# Mixer_to_LP-HP_Filter.net
KiCad netlist of a schematic drawn in Altium Designer
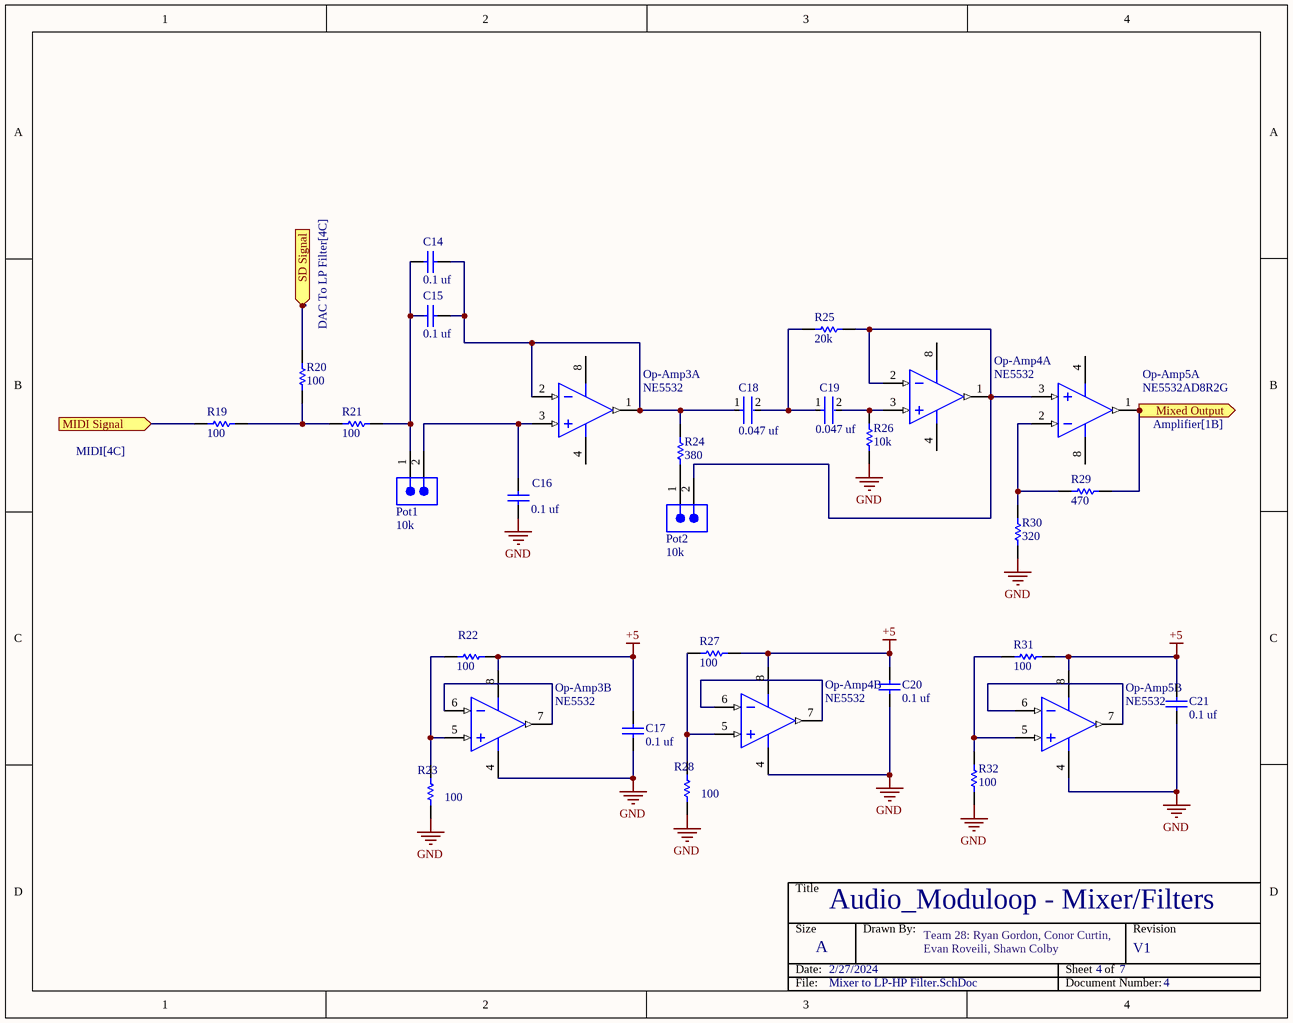
[diagram p0: Mixer to LP-HP Filter.SchDoc]

(export (version "E")
  (design (tool "Eeschema 10.0.6"))
  (components
    (comp (ref "C14")
      (value "0.1 uf")
      (footprint "AVX-SA115C104KAR")
      (fields (field (name "TOLERANCE") "±10%") (field (name "MANUFACTURER") "AVX"))
      (libsource (lib "Altium Content Vault") (part "CAP-NP-2"))
    )
    (comp (ref "C15")
      (value "0.1 uf")
      (footprint "AVX-SA115C104KAR")
      (fields (field (name "TOLERANCE") "±10%") (field (name "MANUFACTURER") "AVX"))
      (libsource (lib "Altium Content Vault") (part "CAP-NP-2"))
    )
    (comp (ref "C16")
      (value "0.1 uf")
      (footprint "AVX-SA115C104KAR")
      (fields (field (name "TOLERANCE") "±10%") (field (name "MANUFACTURER") "AVX"))
      (libsource (lib "Altium Content Vault") (part "CAP-NP-2"))
    )
    (comp (ref "C17")
      (value "0.1 uf")
      (footprint "AVX-SA115C104KAR")
      (fields (field (name "TOLERANCE") "±10%") (field (name "MANUFACTURER") "AVX"))
      (libsource (lib "Altium Content Vault") (part "CAP-NP-2"))
    )
    (comp (ref "C18")
      (value "0.047 uf")
      (footprint "FP-RCE1K1-2_5-MFG")
      (description "Cap Ceramic Monolithic 47nF 100V 10% Thru-Hole Bulk")
      (fields (field (name "TOLERANCE") "10%"))
      (libsource (lib "Altium Content Vault") (part "02cd4be3c70576c341d710602a673aa"))
    )
    (comp (ref "C19")
      (value "0.047 uf")
      (footprint "FP-RCE1K1-2_5-MFG")
      (description "Cap Ceramic Monolithic 47nF 100V 10% Thru-Hole Bulk")
      (fields (field (name "TOLERANCE") "10%"))
      (libsource (lib "Altium Content Vault") (part "02cd4be3c70576c341d710602a673aa"))
    )
    (comp (ref "C20")
      (value "0.1 uf")
      (footprint "AVX-SA115C104KAR")
      (fields (field (name "TOLERANCE") "±10%") (field (name "MANUFACTURER") "AVX"))
      (libsource (lib "Altium Content Vault") (part "CAP-NP-2"))
    )
    (comp (ref "C21")
      (value "0.1 uf")
      (footprint "AVX-SA115C104KAR")
      (fields (field (name "TOLERANCE") "±10%") (field (name "MANUFACTURER") "AVX"))
      (libsource (lib "Altium Content Vault") (part "CAP-NP-2"))
    )
    (comp (ref "Op-Amp3")
      (value "NE5532")
      (footprint "ONSC-SOIC-8-751-07_V")
      (fields (field (name "MANUFACTURER") "On Semiconductor") (field (name "PARTNUMBER") "NE5532AD8R2G"))
      (libsource (lib "Altium Content Vault") (part "ONSC-NE5532-SOIC-8-751-07"))
    )
    (comp (ref "Op-Amp4")
      (value "NE5532")
      (footprint "ONSC-SOIC-8-751-07_V")
      (fields (field (name "MANUFACTURER") "On Semiconductor") (field (name "PARTNUMBER") "NE5532AD8R2G"))
      (libsource (lib "Altium Content Vault") (part "ONSC-NE5532-SOIC-8-751-07"))
    )
    (comp (ref "Op-Amp5")
      (value "NE5532AD8R2G")
      (footprint "ONSC-SOIC-8-751-07_V")
      (fields (field (name "MANUFACTURER") "On Semiconductor") (field (name "PARTNUMBER") "NE5532AD8R2G"))
      (libsource (lib "Altium Content Vault") (part "ONSC-NE5532-SOIC-8-751-07"))
    )
    (comp (ref "Pot1")
      (value "10k")
      (footprint "61300211121")
      (libsource (lib "Altium Content Vault") (part "Header_Male_1R_02P"))
    )
    (comp (ref "Pot2")
      (value "10k")
      (footprint "61300211121")
      (libsource (lib "Altium Content Vault") (part "Header_Male_1R_02P"))
    )
    (comp (ref "R19")
      (value "100")
      (footprint "RESC2013X60X40ML20T25")
      (fields (field (name "MANUFACTURER") "Panasonic") (field (name "PART NUMBER") "ERA6AEB101V"))
      (libsource (lib "Altium Content Vault") (part "RES"))
    )
    (comp (ref "R20")
      (value "100")
      (footprint "RESC2013X60X40ML20T25")
      (fields (field (name "MANUFACTURER") "Panasonic") (field (name "PART NUMBER") "ERA6AEB101V"))
      (libsource (lib "Altium Content Vault") (part "RES"))
    )
    (comp (ref "R21")
      (value "100")
      (footprint "RESC2013X60X40ML20T25")
      (fields (field (name "MANUFACTURER") "Panasonic") (field (name "PART NUMBER") "ERA6AEB101V"))
      (libsource (lib "Altium Content Vault") (part "RES"))
    )
    (comp (ref "R22")
      (value "100")
      (footprint "RESC2013X60X40ML20T25")
      (fields (field (name "MANUFACTURER") "Panasonic") (field (name "PART NUMBER") "ERA6AEB101V"))
      (libsource (lib "Altium Content Vault") (part "RES"))
    )
    (comp (ref "R23")
      (value "100")
      (footprint "RESC2013X60X40ML20T25")
      (fields (field (name "MANUFACTURER") "Panasonic") (field (name "PART NUMBER") "ERA6AEB101V"))
      (libsource (lib "Altium Content Vault") (part "RES"))
    )
    (comp (ref "R24")
      (value "380")
      (footprint "RESC2013X60X40LL20T25")
      (fields (field (name "MANUFACTURER") "Panasonic") (field (name "PART NUMBER") "ERA6AEB331V"))
      (libsource (lib "Altium Content Vault") (part "RES"))
    )
    (comp (ref "R25")
      (value "20k")
      (footprint "RESC2013X60X35NL10T20")
      (description "Chip Resistor, 10 KOhm, +/- 1%, 0.125 W, -55 to 155 degC, 0805 (2012 Metric), RoHS, Tape and Reel")
      (fields (field (name "MANUFACTURER") "Yageo"))
      (libsource (lib "Altium Content Vault") (part "RES-2"))
    )
    (comp (ref "R26")
      (value "10k")
      (footprint "RESC2013X60X35NL10T20")
      (description "Chip Resistor, 10 KOhm, +/- 1%, 0.125 W, -55 to 155 degC, 0805 (2012 Metric), RoHS, Tape and Reel")
      (fields (field (name "MANUFACTURER") "Yageo"))
      (libsource (lib "Altium Content Vault") (part "RES-2"))
    )
    (comp (ref "R27")
      (value "100")
      (footprint "RESC2013X60X40ML20T25")
      (fields (field (name "MANUFACTURER") "Panasonic") (field (name "PART NUMBER") "ERA6AEB101V"))
      (libsource (lib "Altium Content Vault") (part "RES"))
    )
    (comp (ref "R28")
      (value "100")
      (footprint "RESC2013X60X40ML20T25")
      (fields (field (name "MANUFACTURER") "Panasonic") (field (name "PART NUMBER") "ERA6AEB101V"))
      (libsource (lib "Altium Content Vault") (part "RES"))
    )
    (comp (ref "R29")
      (value "470")
      (footprint "RESC2013X60X40NL20T25")
      (fields (field (name "PART NUMBER") "ERA6AEB471V") (field (name "MANUFACTURER") "Panasonic"))
      (libsource (lib "Altium Content Vault") (part "RES"))
    )
    (comp (ref "R30")
      (value "320")
      (footprint "RESC2013X60X40LL20T25")
      (fields (field (name "MANUFACTURER") "Panasonic") (field (name "PART NUMBER") "ERA6AEB331V"))
      (libsource (lib "Altium Content Vault") (part "RES"))
    )
    (comp (ref "R31")
      (value "100")
      (footprint "RESC2013X60X40ML20T25")
      (fields (field (name "MANUFACTURER") "Panasonic") (field (name "PART NUMBER") "ERA6AEB101V"))
      (libsource (lib "Altium Content Vault") (part "RES"))
    )
    (comp (ref "R32")
      (value "100")
      (footprint "RESC2013X60X40ML20T25")
      (fields (field (name "MANUFACTURER") "Panasonic") (field (name "PART NUMBER") "ERA6AEB101V"))
      (libsource (lib "Altium Content Vault") (part "RES"))
    )
  )
  (nets
    (net (code "1") (name "+5") (class "Default")
      (node (ref "C17") (pin "2") (pinfunction "2_2") (pintype "passive"))
      (node (ref "C20") (pin "2") (pinfunction "2_2") (pintype "passive"))
      (node (ref "C21") (pin "2") (pinfunction "2_2") (pintype "passive"))
      (node (ref "Op-Amp3") (pin "8") (pinfunction "V+_8") (pintype "power_in"))
      (node (ref "Op-Amp4") (pin "8") (pinfunction "V+_8") (pintype "power_in"))
      (node (ref "Op-Amp5") (pin "8") (pinfunction "V+_8") (pintype "power_in"))
      (node (ref "R22") (pin "1") (pinfunction "1_1") (pintype "passive"))
      (node (ref "R27") (pin "1") (pinfunction "1_1") (pintype "passive"))
      (node (ref "R31") (pin "1") (pinfunction "1_1") (pintype "passive"))
    )
    (net (code "2") (name "/MIDI Signal") (class "Default")
      (node (ref "R19") (pin "1") (pinfunction "1_1") (pintype "passive"))
    )
    (net (code "3") (name "/Mixed Output") (class "Default")
      (node (ref "Op-Amp5") (pin "1") (pinfunction "OUTA_1") (pintype "output"))
      (node (ref "R29") (pin "2") (pinfunction "2_2") (pintype "passive"))
    )
    (net (code "4") (name "/SD Signal") (class "Default")
      (node (ref "R20") (pin "1") (pinfunction "1_1") (pintype "passive"))
    )
    (net (code "5") (name "GND") (class "Default")
      (node (ref "C16") (pin "1") (pinfunction "1_1") (pintype "passive"))
      (node (ref "C17") (pin "1") (pinfunction "1_1") (pintype "passive"))
      (node (ref "C20") (pin "1") (pinfunction "1_1") (pintype "passive"))
      (node (ref "C21") (pin "1") (pinfunction "1_1") (pintype "passive"))
      (node (ref "Op-Amp3") (pin "4") (pinfunction "V-_4") (pintype "power_in"))
      (node (ref "Op-Amp4") (pin "4") (pinfunction "V-_4") (pintype "power_in"))
      (node (ref "Op-Amp5") (pin "4") (pinfunction "V-_4") (pintype "power_in"))
      (node (ref "R23") (pin "1") (pinfunction "1_1") (pintype "passive"))
      (node (ref "R26") (pin "2") (pinfunction "2_2") (pintype "passive"))
      (node (ref "R28") (pin "1") (pinfunction "1_1") (pintype "passive"))
      (node (ref "R30") (pin "2") (pinfunction "2_2") (pintype "passive"))
      (node (ref "R32") (pin "2") (pinfunction "2_2") (pintype "passive"))
    )
    (net (code "6") (name "Net-(C14-Pad1)") (class "Default")
      (node (ref "C14") (pin "1") (pinfunction "1_1") (pintype "passive"))
      (node (ref "C15") (pin "1") (pinfunction "1_1") (pintype "passive"))
      (node (ref "Pot1") (pin "1") (pinfunction "1_1") (pintype "passive"))
      (node (ref "R21") (pin "1") (pinfunction "1_1") (pintype "passive"))
    )
    (net (code "7") (name "Net-(C18-Pad2)") (class "Default")
      (node (ref "C18") (pin "2") (pinfunction "2_2") (pintype "passive"))
      (node (ref "C19") (pin "1") (pinfunction "1_1") (pintype "passive"))
      (node (ref "R25") (pin "1") (pinfunction "1_1") (pintype "passive"))
    )
    (net (code "8") (name "Net-(Op-Amp3A-INA+)") (class "Default")
      (node (ref "C16") (pin "2") (pinfunction "2_2") (pintype "passive"))
      (node (ref "Op-Amp3") (pin "3") (pinfunction "INA+_3") (pintype "input"))
      (node (ref "Pot1") (pin "2") (pinfunction "2_2") (pintype "passive"))
    )
    (net (code "9") (name "Net-(Op-Amp3A-INA-)") (class "Default")
      (node (ref "C14") (pin "2") (pinfunction "2_2") (pintype "passive"))
      (node (ref "C15") (pin "2") (pinfunction "2_2") (pintype "passive"))
      (node (ref "C18") (pin "1") (pinfunction "1_1") (pintype "passive"))
      (node (ref "Op-Amp3") (pin "1") (pinfunction "OUTA_1") (pintype "output"))
      (node (ref "Op-Amp3") (pin "2") (pinfunction "INA-_2") (pintype "input"))
      (node (ref "R24") (pin "1") (pinfunction "1_1") (pintype "passive"))
    )
    (net (code "10") (name "Net-(Op-Amp3B-INB+)") (class "Default")
      (node (ref "Op-Amp3") (pin "5") (pinfunction "INB+_5") (pintype "input"))
      (node (ref "R22") (pin "2") (pinfunction "2_2") (pintype "passive"))
      (node (ref "R23") (pin "2") (pinfunction "2_2") (pintype "passive"))
    )
    (net (code "11") (name "Net-(Op-Amp3B-INB-)") (class "Default")
      (node (ref "Op-Amp3") (pin "6") (pinfunction "INB-_6") (pintype "input"))
      (node (ref "Op-Amp3") (pin "7") (pinfunction "OUTB_7") (pintype "output"))
    )
    (net (code "12") (name "Net-(Op-Amp4A-INA+)") (class "Default")
      (node (ref "C19") (pin "2") (pinfunction "2_2") (pintype "passive"))
      (node (ref "Op-Amp4") (pin "3") (pinfunction "INA+_3") (pintype "input"))
      (node (ref "R26") (pin "1") (pinfunction "1_1") (pintype "passive"))
    )
    (net (code "13") (name "Net-(Op-Amp4A-INA-)") (class "Default")
      (node (ref "Op-Amp4") (pin "1") (pinfunction "OUTA_1") (pintype "output"))
      (node (ref "Op-Amp4") (pin "2") (pinfunction "INA-_2") (pintype "input"))
      (node (ref "Op-Amp5") (pin "3") (pinfunction "INA+_3") (pintype "input"))
      (node (ref "Pot2") (pin "2") (pinfunction "2_2") (pintype "passive"))
      (node (ref "R25") (pin "2") (pinfunction "2_2") (pintype "passive"))
    )
    (net (code "14") (name "Net-(Op-Amp4B-INB+)") (class "Default")
      (node (ref "Op-Amp4") (pin "5") (pinfunction "INB+_5") (pintype "input"))
      (node (ref "R27") (pin "2") (pinfunction "2_2") (pintype "passive"))
      (node (ref "R28") (pin "2") (pinfunction "2_2") (pintype "passive"))
    )
    (net (code "15") (name "Net-(Op-Amp4B-INB-)") (class "Default")
      (node (ref "Op-Amp4") (pin "6") (pinfunction "INB-_6") (pintype "input"))
      (node (ref "Op-Amp4") (pin "7") (pinfunction "OUTB_7") (pintype "output"))
    )
    (net (code "16") (name "Net-(Op-Amp5A-INA-)") (class "Default")
      (node (ref "Op-Amp5") (pin "2") (pinfunction "INA-_2") (pintype "input"))
      (node (ref "R29") (pin "1") (pinfunction "1_1") (pintype "passive"))
      (node (ref "R30") (pin "1") (pinfunction "1_1") (pintype "passive"))
    )
    (net (code "17") (name "Net-(Op-Amp5B-INB+)") (class "Default")
      (node (ref "Op-Amp5") (pin "5") (pinfunction "INB+_5") (pintype "input"))
      (node (ref "R31") (pin "2") (pinfunction "2_2") (pintype "passive"))
      (node (ref "R32") (pin "1") (pinfunction "1_1") (pintype "passive"))
    )
    (net (code "18") (name "Net-(Op-Amp5B-INB-)") (class "Default")
      (node (ref "Op-Amp5") (pin "6") (pinfunction "INB-_6") (pintype "input"))
      (node (ref "Op-Amp5") (pin "7") (pinfunction "OUTB_7") (pintype "output"))
    )
    (net (code "19") (name "Net-(Pot2-Pad1)") (class "Default")
      (node (ref "Pot2") (pin "1") (pinfunction "1_1") (pintype "passive"))
      (node (ref "R24") (pin "2") (pinfunction "2_2") (pintype "passive"))
    )
    (net (code "20") (name "Net-(R19-Pad2)") (class "Default")
      (node (ref "R19") (pin "2") (pinfunction "2_2") (pintype "passive"))
      (node (ref "R20") (pin "2") (pinfunction "2_2") (pintype "passive"))
      (node (ref "R21") (pin "2") (pinfunction "2_2") (pintype "passive"))
    )
    (net (code "21") (name "unconnected-(Op-Amp3A-V+-Pad8)") (class "Default")
      (node (ref "Op-Amp3") (pin "8") (pinfunction "V+_8") (pintype "power_in"))
    )
    (net (code "22") (name "unconnected-(Op-Amp3A-V--Pad4)") (class "Default")
      (node (ref "Op-Amp3") (pin "4") (pinfunction "V-_4") (pintype "power_in"))
    )
    (net (code "23") (name "unconnected-(Op-Amp4A-V+-Pad8)") (class "Default")
      (node (ref "Op-Amp4") (pin "8") (pinfunction "V+_8") (pintype "power_in"))
    )
    (net (code "24") (name "unconnected-(Op-Amp4A-V--Pad4)") (class "Default")
      (node (ref "Op-Amp4") (pin "4") (pinfunction "V-_4") (pintype "power_in"))
    )
    (net (code "25") (name "unconnected-(Op-Amp5A-V+-Pad8)") (class "Default")
      (node (ref "Op-Amp5") (pin "8") (pinfunction "V+_8") (pintype "power_in"))
    )
    (net (code "26") (name "unconnected-(Op-Amp5A-V--Pad4)") (class "Default")
      (node (ref "Op-Amp5") (pin "4") (pinfunction "V-_4") (pintype "power_in"))
    )
  )
)
